# Striso_audio_mixer.net
KiCad netlist of a schematic drawn in EasyEDA Pro
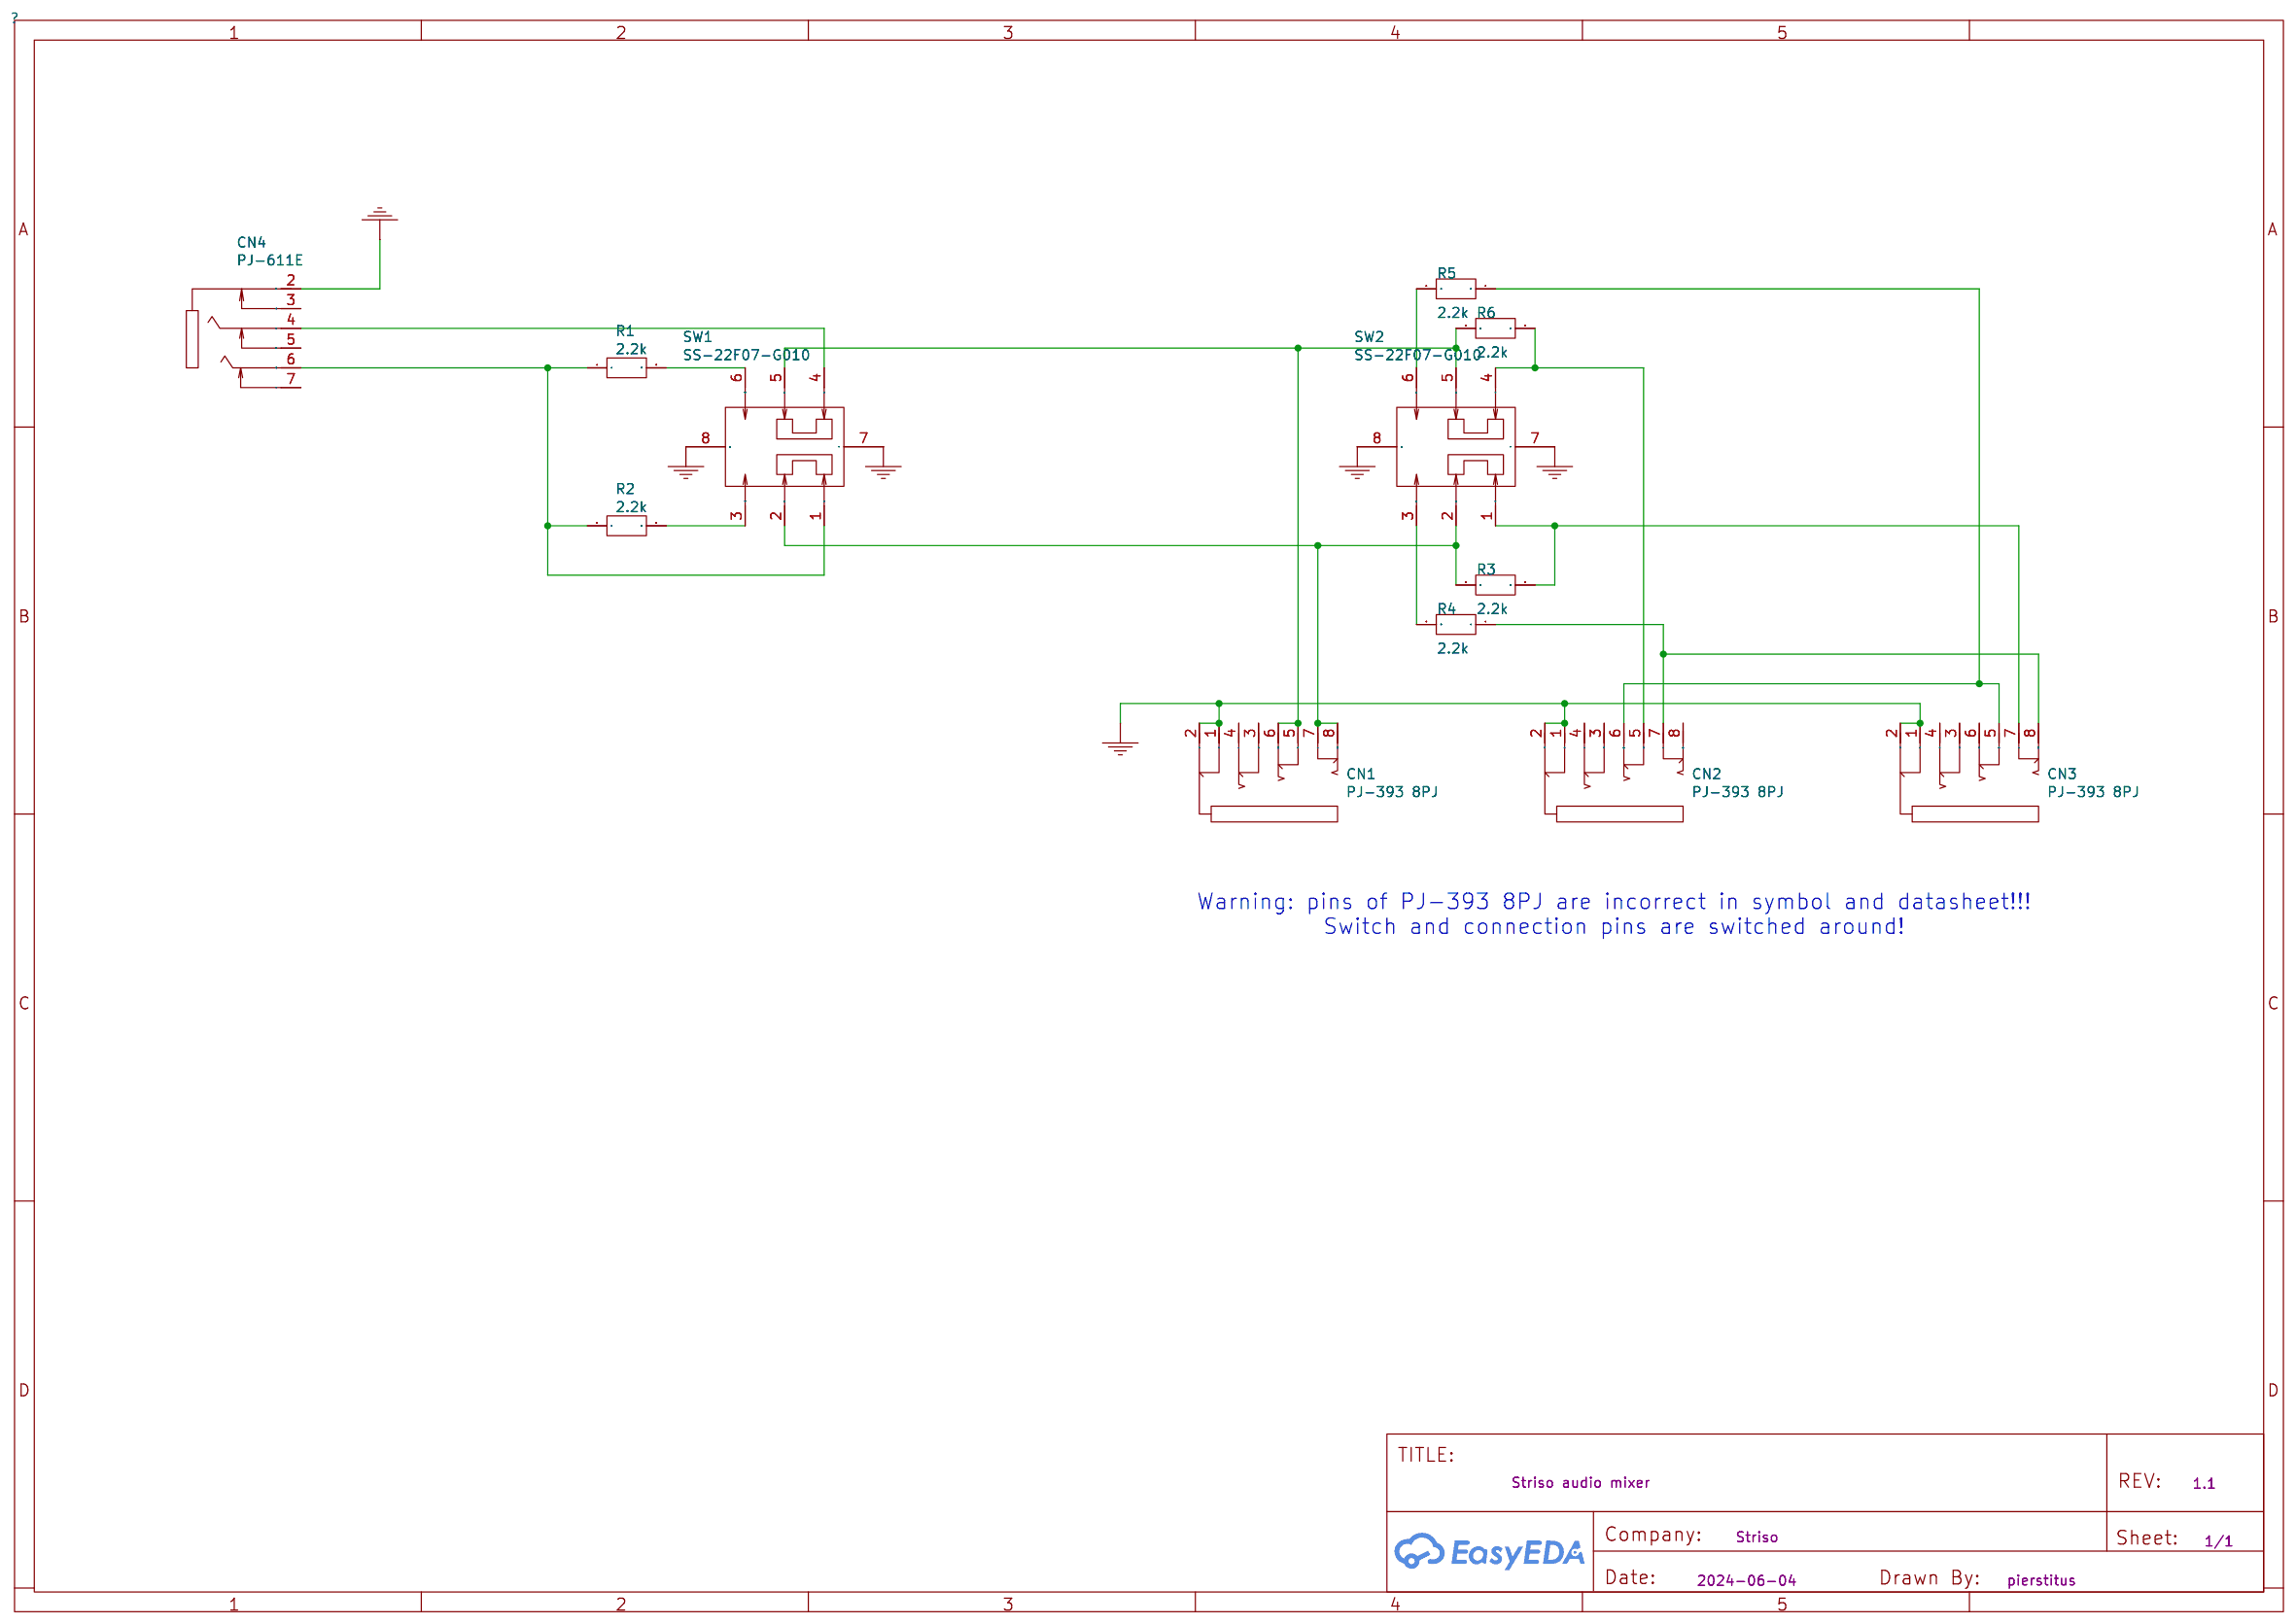
[diagram p0: schematic sheet]

(export (version "E")
  (design (tool "Eeschema 10.0.6"))
  (components
    (comp (ref "CN1")
      (value "PJ-393 8PJ")
      (footprint "easyedapro:AUDIO-SMD_PJ-393-8PJ")
      (fields (field (name "Manufacturer") "SHOU HAN(首韩)"))
      (libsource (lib "easyedapro") (part "PJ-393 8PJ"))
    )
    (comp (ref "CN2")
      (value "PJ-393 8PJ")
      (footprint "easyedapro:AUDIO-SMD_PJ-393-8PJ")
      (fields (field (name "Manufacturer") "SHOU HAN(首韩)"))
      (libsource (lib "easyedapro") (part "PJ-393 8PJ"))
    )
    (comp (ref "CN3")
      (value "PJ-393 8PJ")
      (footprint "easyedapro:AUDIO-SMD_PJ-393-8PJ")
      (fields (field (name "Manufacturer") "SHOU HAN(首韩)"))
      (libsource (lib "easyedapro") (part "PJ-393 8PJ"))
    )
    (comp (ref "CN4")
      (value "PJ-611E")
      (footprint "easyedapro:AUDIO-TH_PJ-611E")
      (fields (field (name "Manufacturer") "HOOYA(皓宇电子)"))
      (libsource (lib "easyedapro") (part "PJ-611E"))
    )
    (comp (ref "R1")
      (value "2.2k")
      (footprint "easyedapro:R0603")
      (libsource (lib "easyedapro") (part "2.2k"))
    )
    (comp (ref "R2")
      (value "2.2k")
      (footprint "easyedapro:R0603")
      (libsource (lib "easyedapro") (part "2.2k"))
    )
    (comp (ref "R3")
      (value "2.2k")
      (footprint "easyedapro:R0603")
      (libsource (lib "easyedapro") (part "2.2k"))
    )
    (comp (ref "R4")
      (value "2.2k")
      (footprint "easyedapro:R0603")
      (libsource (lib "easyedapro") (part "2.2k"))
    )
    (comp (ref "R5")
      (value "2.2k")
      (footprint "easyedapro:R0603")
      (libsource (lib "easyedapro") (part "2.2k"))
    )
    (comp (ref "R6")
      (value "2.2k")
      (footprint "easyedapro:R0603")
      (libsource (lib "easyedapro") (part "2.2k"))
    )
    (comp (ref "SW1")
      (value "SS-22F07-G010")
      (footprint "easyedapro:SW-TH_6P-L16.5-W7.5-P4.0-LS2.6-TL")
      (fields (field (name "Manufacturer") "G-Switch(品赞)"))
      (libsource (lib "easyedapro") (part "SS-22F07-G010"))
    )
    (comp (ref "SW2")
      (value "SS-22F07-G010")
      (footprint "easyedapro:SW-TH_6P-L16.5-W7.5-P4.0-LS2.6-TL")
      (fields (field (name "Manufacturer") "G-Switch(品赞)"))
      (libsource (lib "easyedapro") (part "SS-22F07-G010"))
    )
  )
  (nets
    (net (code "1") (name "GND") (class "Default")
      (node (ref "CN1") (pin "1") (pinfunction "1_1") (pintype "unspecified"))
      (node (ref "CN1") (pin "2") (pinfunction "2_2") (pintype "unspecified"))
      (node (ref "CN2") (pin "1") (pinfunction "1_1") (pintype "unspecified"))
      (node (ref "CN2") (pin "2") (pinfunction "2_2") (pintype "unspecified"))
      (node (ref "CN3") (pin "1") (pinfunction "1_1") (pintype "unspecified"))
      (node (ref "CN3") (pin "2") (pinfunction "2_2") (pintype "unspecified"))
      (node (ref "CN4") (pin "2") (pinfunction "2_2") (pintype "unspecified"))
      (node (ref "SW1") (pin "7") (pinfunction "7_7") (pintype "unspecified"))
      (node (ref "SW1") (pin "8") (pinfunction "8_8") (pintype "unspecified"))
      (node (ref "SW2") (pin "7") (pinfunction "7_7") (pintype "unspecified"))
      (node (ref "SW2") (pin "8") (pinfunction "8_8") (pintype "unspecified"))
    )
    (net (code "2") (name "Net-(CN1-Pad5)") (class "Default")
      (node (ref "CN1") (pin "5") (pinfunction "5_5") (pintype "unspecified"))
      (node (ref "CN1") (pin "6") (pinfunction "6_6") (pintype "unspecified"))
      (node (ref "R6") (pin "2") (pinfunction "2_2") (pintype "unspecified"))
      (node (ref "SW1") (pin "5") (pinfunction "5_5") (pintype "unspecified"))
      (node (ref "SW2") (pin "5") (pinfunction "5_5") (pintype "unspecified"))
    )
    (net (code "3") (name "Net-(CN1-Pad7)") (class "Default")
      (node (ref "CN1") (pin "7") (pinfunction "7_7") (pintype "unspecified"))
      (node (ref "CN1") (pin "8") (pinfunction "8_8") (pintype "unspecified"))
      (node (ref "R3") (pin "2") (pinfunction "2_2") (pintype "unspecified"))
      (node (ref "SW1") (pin "2") (pinfunction "2_2") (pintype "unspecified"))
      (node (ref "SW2") (pin "2") (pinfunction "2_2") (pintype "unspecified"))
    )
    (net (code "4") (name "Net-(CN2-Pad5)") (class "Default")
      (node (ref "CN2") (pin "5") (pinfunction "5_5") (pintype "unspecified"))
      (node (ref "R6") (pin "1") (pinfunction "1_1") (pintype "unspecified"))
      (node (ref "SW2") (pin "4") (pinfunction "4_4") (pintype "unspecified"))
    )
    (net (code "5") (name "Net-(CN2-Pad6)") (class "Default")
      (node (ref "CN2") (pin "6") (pinfunction "6_6") (pintype "unspecified"))
      (node (ref "CN3") (pin "5") (pinfunction "5_5") (pintype "unspecified"))
      (node (ref "R5") (pin "1") (pinfunction "1_1") (pintype "unspecified"))
    )
    (net (code "6") (name "Net-(CN2-Pad7)") (class "Default")
      (node (ref "CN2") (pin "7") (pinfunction "7_7") (pintype "unspecified"))
      (node (ref "CN3") (pin "8") (pinfunction "8_8") (pintype "unspecified"))
      (node (ref "R4") (pin "1") (pinfunction "1_1") (pintype "unspecified"))
    )
    (net (code "7") (name "Net-(CN3-Pad7)") (class "Default")
      (node (ref "CN3") (pin "7") (pinfunction "7_7") (pintype "unspecified"))
      (node (ref "R3") (pin "1") (pinfunction "1_1") (pintype "unspecified"))
      (node (ref "SW2") (pin "1") (pinfunction "1_1") (pintype "unspecified"))
    )
    (net (code "8") (name "Net-(CN4-Pad4)") (class "Default")
      (node (ref "CN4") (pin "4") (pinfunction "4_4") (pintype "unspecified"))
      (node (ref "SW1") (pin "4") (pinfunction "4_4") (pintype "unspecified"))
    )
    (net (code "9") (name "Net-(CN4-Pad6)") (class "Default")
      (node (ref "CN4") (pin "6") (pinfunction "6_6") (pintype "unspecified"))
      (node (ref "R1") (pin "1") (pinfunction "1_1") (pintype "unspecified"))
      (node (ref "R2") (pin "1") (pinfunction "1_1") (pintype "unspecified"))
      (node (ref "SW1") (pin "1") (pinfunction "1_1") (pintype "unspecified"))
    )
    (net (code "10") (name "Net-(R1-Pad2)") (class "Default")
      (node (ref "R1") (pin "2") (pinfunction "2_2") (pintype "unspecified"))
      (node (ref "SW1") (pin "6") (pinfunction "6_6") (pintype "unspecified"))
    )
    (net (code "11") (name "Net-(R2-Pad2)") (class "Default")
      (node (ref "R2") (pin "2") (pinfunction "2_2") (pintype "unspecified"))
      (node (ref "SW1") (pin "3") (pinfunction "3_3") (pintype "unspecified"))
    )
    (net (code "12") (name "Net-(R4-Pad2)") (class "Default")
      (node (ref "R4") (pin "2") (pinfunction "2_2") (pintype "unspecified"))
      (node (ref "SW2") (pin "3") (pinfunction "3_3") (pintype "unspecified"))
    )
    (net (code "13") (name "Net-(R5-Pad2)") (class "Default")
      (node (ref "R5") (pin "2") (pinfunction "2_2") (pintype "unspecified"))
      (node (ref "SW2") (pin "6") (pinfunction "6_6") (pintype "unspecified"))
    )
    (net (code "14") (name "unconnected-(CN1-Pad3)") (class "Default")
      (node (ref "CN1") (pin "3") (pinfunction "3_3") (pintype "unspecified"))
    )
    (net (code "15") (name "unconnected-(CN1-Pad4)") (class "Default")
      (node (ref "CN1") (pin "4") (pinfunction "4_4") (pintype "unspecified"))
    )
    (net (code "16") (name "unconnected-(CN2-Pad3)") (class "Default")
      (node (ref "CN2") (pin "3") (pinfunction "3_3") (pintype "unspecified"))
    )
    (net (code "17") (name "unconnected-(CN2-Pad4)") (class "Default")
      (node (ref "CN2") (pin "4") (pinfunction "4_4") (pintype "unspecified"))
    )
    (net (code "18") (name "unconnected-(CN2-Pad8)") (class "Default")
      (node (ref "CN2") (pin "8") (pinfunction "8_8") (pintype "unspecified"))
    )
    (net (code "19") (name "unconnected-(CN3-Pad3)") (class "Default")
      (node (ref "CN3") (pin "3") (pinfunction "3_3") (pintype "unspecified"))
    )
    (net (code "20") (name "unconnected-(CN3-Pad4)") (class "Default")
      (node (ref "CN3") (pin "4") (pinfunction "4_4") (pintype "unspecified"))
    )
    (net (code "21") (name "unconnected-(CN3-Pad6)") (class "Default")
      (node (ref "CN3") (pin "6") (pinfunction "6_6") (pintype "unspecified"))
    )
    (net (code "22") (name "unconnected-(CN4-Pad3)") (class "Default")
      (node (ref "CN4") (pin "3") (pinfunction "3_3") (pintype "unspecified"))
    )
    (net (code "23") (name "unconnected-(CN4-Pad5)") (class "Default")
      (node (ref "CN4") (pin "5") (pinfunction "5_5") (pintype "unspecified"))
    )
    (net (code "24") (name "unconnected-(CN4-Pad7)") (class "Default")
      (node (ref "CN4") (pin "7") (pinfunction "7_7") (pintype "unspecified"))
    )
  )
)
